# RX.net
KiCad netlist of a schematic drawn in Altium Designer
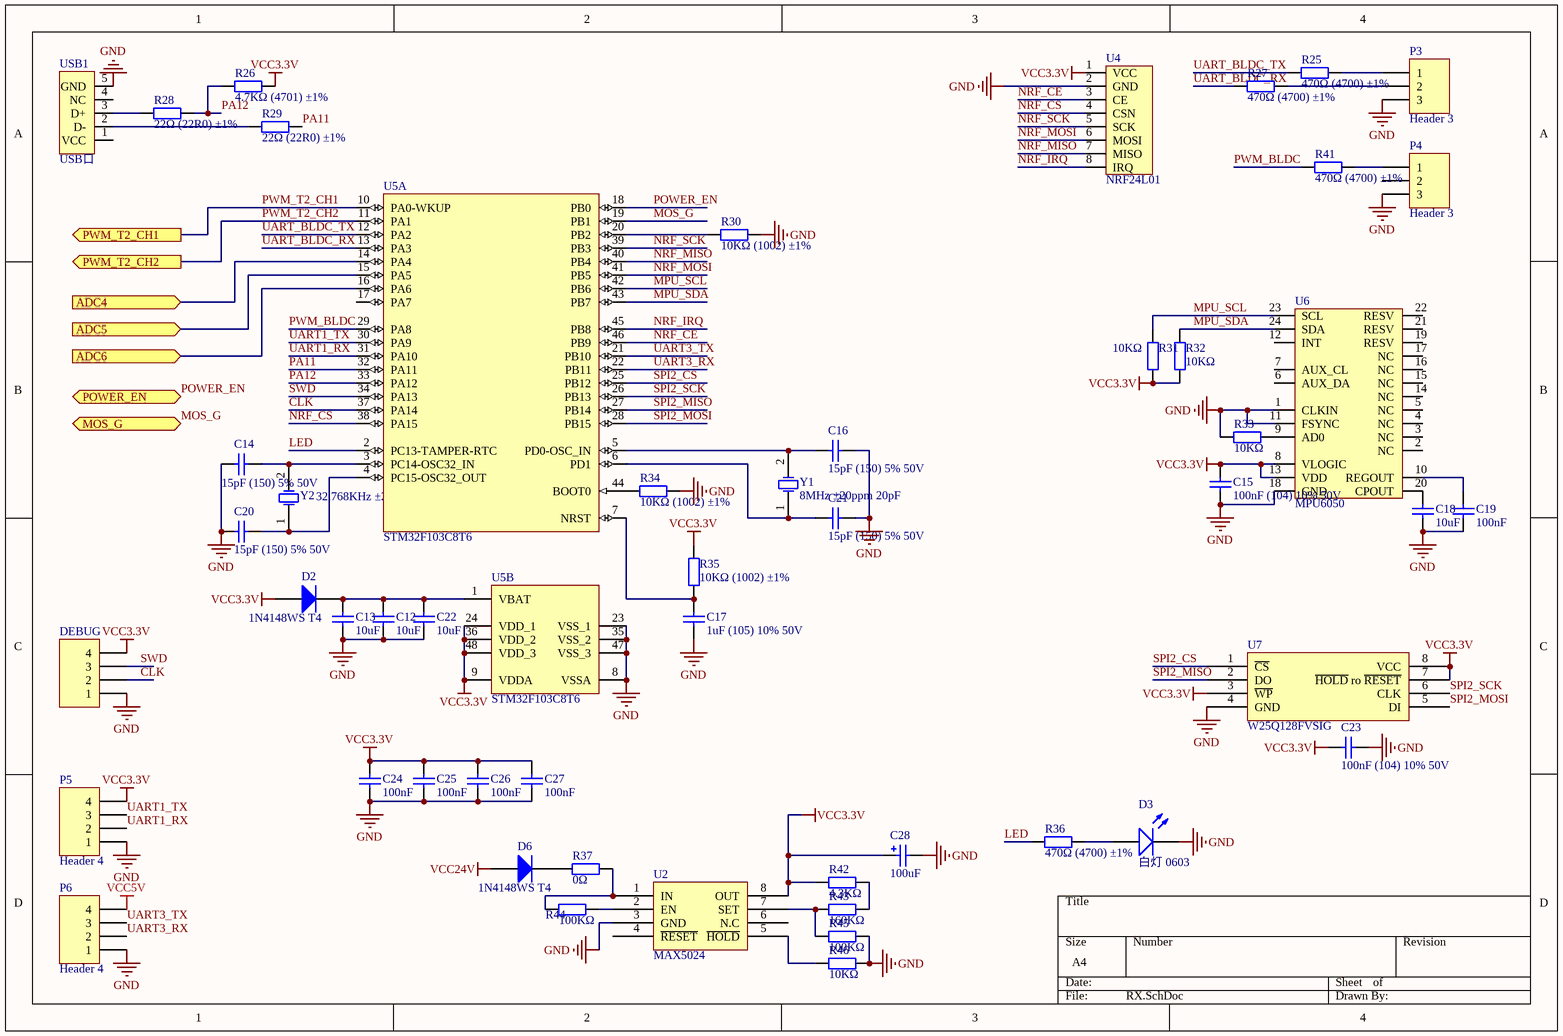
[diagram p0: RX.SchDoc]

(export (version "E")
  (design (tool "Eeschema 10.0.6"))
  (components
    (comp (ref "C12")
      (value "10uF")
      (footprint "0603_C")
      (description "贴片电容")
      (libsource (lib "Miscellaneous Devices LC") (part "0603 10uF (106) 10% 10V"))
    )
    (comp (ref "C13")
      (value "10uF")
      (footprint "0603_C")
      (description "贴片电容")
      (libsource (lib "Miscellaneous Devices LC") (part "0603 10uF (106) 10% 10V"))
    )
    (comp (ref "C14")
      (value "15pF (150) 5% 50V")
      (footprint "0603_C")
      (description "贴片电容")
      (libsource (lib "Miscellaneous Devices LC") (part "0603 15pF (150) 5% 50V"))
    )
    (comp (ref "C15")
      (value "100nF (104) 10% 50V")
      (footprint "0603_C")
      (description "贴片电容")
      (libsource (lib "Miscellaneous Devices LC") (part "0603 100nF (104) 10% 50V"))
    )
    (comp (ref "C16")
      (value "15pF (150) 5% 50V")
      (footprint "0603_C")
      (description "贴片电容")
      (libsource (lib "Miscellaneous Devices LC") (part "0603 15pF (150) 5% 50V"))
    )
    (comp (ref "C17")
      (value "1uF (105) 10% 50V")
      (footprint "0603_C")
      (description "贴片电容")
      (libsource (lib "Miscellaneous Devices LC") (part "0603 1uF (105) 10% 50V"))
    )
    (comp (ref "C18")
      (value "10uF")
      (footprint "0603_C")
      (description "贴片电容")
      (libsource (lib "Miscellaneous Devices LC") (part "0603 10uF (106) 10% 10V"))
    )
    (comp (ref "C19")
      (value "100nF")
      (footprint "0603_C")
      (description "贴片电容")
      (libsource (lib "Miscellaneous Devices LC") (part "0603 100nF (104) 10% 50V"))
    )
    (comp (ref "C20")
      (value "15pF (150) 5% 50V")
      (footprint "0603_C")
      (description "贴片电容")
      (libsource (lib "Miscellaneous Devices LC") (part "0603 15pF (150) 5% 50V"))
    )
    (comp (ref "C21")
      (value "15pF (150) 5% 50V")
      (footprint "0603_C")
      (description "贴片电容")
      (libsource (lib "Miscellaneous Devices LC") (part "0603 15pF (150) 5% 50V"))
    )
    (comp (ref "C22")
      (value "10uF")
      (footprint "0603_C")
      (description "贴片电容")
      (libsource (lib "Miscellaneous Devices LC") (part "0603 10uF (106) 10% 10V"))
    )
    (comp (ref "C23")
      (value "100nF (104) 10% 50V")
      (footprint "0603_C")
      (description "贴片电容")
      (libsource (lib "Miscellaneous Devices LC") (part "0603 100nF (104) 10% 50V"))
    )
    (comp (ref "C24")
      (value "100nF")
      (footprint "0603_C")
      (description "贴片电容")
      (libsource (lib "Miscellaneous Devices LC") (part "0603 100nF (104) 10% 50V"))
    )
    (comp (ref "C25")
      (value "100nF")
      (footprint "0603_C")
      (description "贴片电容")
      (libsource (lib "Miscellaneous Devices LC") (part "0603 100nF (104) 10% 50V"))
    )
    (comp (ref "C26")
      (value "100nF")
      (footprint "0603_C")
      (description "贴片电容")
      (libsource (lib "Miscellaneous Devices LC") (part "0603 100nF (104) 10% 50V"))
    )
    (comp (ref "C27")
      (value "100nF")
      (footprint "0603_C")
      (description "贴片电容")
      (libsource (lib "Miscellaneous Devices LC") (part "0603 100nF (104) 10% 50V"))
    )
    (comp (ref "C28")
      (value "100uF")
      (footprint "CASE-B_3528")
      (description "钽电容")
      (libsource (lib "Miscellaneous Devices LC") (part "3528 100uF (107) 10% 6.3V"))
    )
    (comp (ref "D2")
      (value "1N4148WS T4")
      (footprint "SOD-323")
      (description "二极管")
      (libsource (lib "Miscellaneous Devices LC") (part "SOD-323 1N4148WS T4"))
    )
    (comp (ref "D3")
      (value "白灯 0603")
      (footprint "0603_LED_S1")
      (description "发光二极管")
      (libsource (lib "Miscellaneous Devices LC") (part "0603 白灯"))
    )
    (comp (ref "D6")
      (value "1N4148WS T4")
      (footprint "SOD-323")
      (description "二极管")
      (libsource (lib "Miscellaneous Devices LC") (part "SOD-323 1N4148WS T4"))
    )
    (comp (ref "DEBUG")
      (value "Header 4")
      (footprint "HDR1X4")
      (description "Header, 4-Pin")
      (fields (field (name "PUBLISHER") "Altium Limited"))
      (libsource (lib "Miscellaneous Connectors") (part "Header 4"))
    )
    (comp (ref "P3")
      (value "Header 3")
      (footprint "HDR1X3")
      (description "Header, 3-Pin")
      (fields (field (name "PUBLISHER") "Altium Limited"))
      (libsource (lib "Miscellaneous Connectors") (part "Header 3"))
    )
    (comp (ref "P4")
      (value "Header 3")
      (footprint "HDR1X3")
      (description "Header, 3-Pin")
      (fields (field (name "PUBLISHER") "Altium Limited"))
      (libsource (lib "Miscellaneous Connectors") (part "Header 3"))
    )
    (comp (ref "P5")
      (value "Header 4")
      (footprint "HDR1X4")
      (description "Header, 4-Pin")
      (fields (field (name "PUBLISHER") "Altium Limited"))
      (libsource (lib "Miscellaneous Connectors") (part "Header 4"))
    )
    (comp (ref "P6")
      (value "Header 4")
      (footprint "HDR1X4")
      (description "Header, 4-Pin")
      (fields (field (name "PUBLISHER") "Altium Limited"))
      (libsource (lib "Miscellaneous Connectors") (part "Header 4"))
    )
    (comp (ref "R25")
      (value "470Ω (4700) ±1%")
      (footprint "0603_R")
      (description "贴片电阻")
      (libsource (lib "Miscellaneous Devices LC") (part "0603 470Ω (4700) 1%"))
    )
    (comp (ref "R26")
      (value "4.7KΩ (4701) ±1%")
      (footprint "0603_R")
      (description "贴片电阻")
      (libsource (lib "Miscellaneous Devices LC") (part "0603 4.7KΩ (4701) 1%"))
    )
    (comp (ref "R27")
      (value "470Ω (4700) ±1%")
      (footprint "0603_R")
      (description "贴片电阻")
      (libsource (lib "Miscellaneous Devices LC") (part "0603 470Ω (4700) 1%"))
    )
    (comp (ref "R28")
      (value "22Ω (22R0) ±1%")
      (footprint "0603_R")
      (description "贴片电阻")
      (libsource (lib "Miscellaneous Devices LC") (part "0603 22Ω (22R0) 1%"))
    )
    (comp (ref "R29")
      (value "22Ω (22R0) ±1%")
      (footprint "0603_R")
      (description "贴片电阻")
      (libsource (lib "Miscellaneous Devices LC") (part "0603 22Ω (22R0) 1%"))
    )
    (comp (ref "R30")
      (value "10KΩ (1002) ±1%")
      (footprint "0603_R")
      (description "贴片电阻")
      (libsource (lib "Miscellaneous Devices LC") (part "0603 10KΩ (1002) 1%"))
    )
    (comp (ref "R31")
      (value "10KΩ")
      (footprint "0603_R")
      (description "贴片电阻")
      (libsource (lib "") (part "0603 10KΩ (1002) 1%_1"))
    )
    (comp (ref "R32")
      (value "10KΩ")
      (footprint "0603_R")
      (description "贴片电阻")
      (libsource (lib "") (part "0603 10KΩ (1002) 1%_2"))
    )
    (comp (ref "R33")
      (value "10KΩ")
      (footprint "0603_R")
      (description "贴片电阻")
      (libsource (lib "Miscellaneous Devices LC") (part "0603 10KΩ (1002) 1%"))
    )
    (comp (ref "R34")
      (value "10KΩ (1002) ±1%")
      (footprint "0603_R")
      (description "贴片电阻")
      (libsource (lib "Miscellaneous Devices LC") (part "0603 10KΩ (1002) 1%"))
    )
    (comp (ref "R35")
      (value "10KΩ (1002) ±1%")
      (footprint "0603_R")
      (description "贴片电阻")
      (libsource (lib "") (part "0603 10KΩ (1002) 1%_1"))
    )
    (comp (ref "R36")
      (value "470Ω (4700) ±1%")
      (footprint "0603_R")
      (description "贴片电阻")
      (libsource (lib "Miscellaneous Devices LC") (part "0603 470Ω (4700) 1%"))
    )
    (comp (ref "R37")
      (value "0Ω")
      (footprint "0805_R")
      (description "贴片电阻")
      (libsource (lib "Miscellaneous Devices LC") (part "0805 0Ω (0R0) 1%"))
    )
    (comp (ref "R41")
      (value "470Ω (4700) ±1%")
      (footprint "0603_R")
      (description "贴片电阻")
      (libsource (lib "Miscellaneous Devices LC") (part "0603 470Ω (4700) 1%"))
    )
    (comp (ref "R42")
      (value "4.3KΩ")
      (footprint "0603_R")
      (description "贴片电阻")
      (libsource (lib "Miscellaneous Devices LC") (part "0603 4.3KΩ (4301) 1%"))
    )
    (comp (ref "R43")
      (value "160KΩ")
      (footprint "0603_R")
      (description "贴片电阻")
      (libsource (lib "Miscellaneous Devices LC") (part "0603 160KΩ (1603) 1%"))
    )
    (comp (ref "R44")
      (value "100KΩ")
      (footprint "0603_R")
      (description "贴片电阻")
      (libsource (lib "Miscellaneous Devices LC") (part "0603 100KΩ (1003) 1%"))
    )
    (comp (ref "R45")
      (value "100KΩ")
      (footprint "0603_R")
      (description "贴片电阻")
      (libsource (lib "Miscellaneous Devices LC") (part "0603 100KΩ (1003) 1%"))
    )
    (comp (ref "R46")
      (value "10KΩ")
      (footprint "0603_R")
      (description "贴片电阻")
      (libsource (lib "Miscellaneous Devices LC") (part "0603 10KΩ (1002) 1%"))
    )
    (comp (ref "U2")
      (value "MAX5024")
      (footprint "SOIC-8_EP_150mil")
      (description "LDO 65Vmax")
      (libsource (lib "MySchlib") (part "MAX5024"))
    )
    (comp (ref "U4")
      (value "NRF24L01")
      (footprint "miniNRF24L01")
      (libsource (lib "MySchlib") (part "NRF24L01"))
    )
    (comp (ref "U5")
      (value "STM32F103C8T6")
      (footprint "LQFP-48_7x7x05P")
      (description "ARM")
      (libsource (lib "Miscellaneous Devices LC") (part "STM32F103C8T6"))
    )
    (comp (ref "U6")
      (value "MPU6050")
      (footprint "QFN24")
      (description "9轴运动处理传感器")
      (libsource (lib "MySchlib") (part "MPU6050"))
    )
    (comp (ref "U7")
      (value "W25Q128FVSIG")
      (footprint "SOIC-8_208mil")
      (description "Flash ROM")
      (libsource (lib "Miscellaneous Devices LC") (part "W25Q128FVSIG"))
    )
    (comp (ref "USB1") (value "USB口") (footprint "MICRO USB") (libsource (lib "MySchlib") (part "USB口")))
    (comp (ref "Y1")
      (value "8MHz ±20ppm 20pF")
      (footprint "SMD-3215_2P FC - 135")
      (description "贴片晶振")
      (libsource (lib "Miscellaneous Devices LC") (part "SMD-5032_2P 8MHz 20ppm 20pF"))
    )
    (comp (ref "Y2")
      (value "32.768KHz ±20ppm 12.5pF")
      (footprint "SMD-3215_2P FC - 135")
      (description "贴片晶振")
      (libsource (lib "Miscellaneous Devices LC") (part "SMD-3215_2P 32.768KHz 20ppm 12.5pF"))
    )
  )
  (nets
    (net (code "1") (name "/ADC4") (class "Default")
      (node (ref "U5") (pin "14") (pinfunction "PA4_14") (pintype "bidirectional"))
    )
    (net (code "2") (name "/ADC5") (class "Default")
      (node (ref "U5") (pin "15") (pinfunction "PA5_15") (pintype "bidirectional"))
    )
    (net (code "3") (name "/ADC6") (class "Default")
      (node (ref "U5") (pin "16") (pinfunction "PA6_16") (pintype "bidirectional"))
    )
    (net (code "4") (name "/CLK") (class "Default")
      (node (ref "DEBUG") (pin "2") (pinfunction "2_2") (pintype "passive"))
      (node (ref "U5") (pin "37") (pinfunction "PA14_37") (pintype "bidirectional"))
    )
    (net (code "5") (name "/LED") (class "Default")
      (node (ref "R36") (pin "1") (pinfunction "1_1") (pintype "passive"))
      (node (ref "U5") (pin "2") (pinfunction "PC13-TAMPER-RTC_2") (pintype "bidirectional"))
    )
    (net (code "6") (name "/MOS_G") (class "Default")
      (node (ref "U5") (pin "19") (pinfunction "PB1_19") (pintype "bidirectional"))
    )
    (net (code "7") (name "/MPU_SCL") (class "Default")
      (node (ref "R31") (pin "2") (pinfunction "2_2") (pintype "passive"))
      (node (ref "U5") (pin "42") (pinfunction "PB6_42") (pintype "bidirectional"))
      (node (ref "U6") (pin "23") (pinfunction "SCL_23") (pintype "passive"))
    )
    (net (code "8") (name "/MPU_SDA") (class "Default")
      (node (ref "R32") (pin "1") (pinfunction "1_1") (pintype "passive"))
      (node (ref "U5") (pin "43") (pinfunction "PB7_43") (pintype "bidirectional"))
      (node (ref "U6") (pin "24") (pinfunction "SDA_24") (pintype "passive"))
    )
    (net (code "9") (name "/NRF_CE") (class "Default")
      (node (ref "U4") (pin "3") (pinfunction "CE_3") (pintype "passive"))
      (node (ref "U5") (pin "46") (pinfunction "PB9_46") (pintype "bidirectional"))
    )
    (net (code "10") (name "/NRF_CS") (class "Default")
      (node (ref "U4") (pin "4") (pinfunction "CSN_4") (pintype "passive"))
      (node (ref "U5") (pin "38") (pinfunction "PA15_38") (pintype "bidirectional"))
    )
    (net (code "11") (name "/NRF_IRQ") (class "Default")
      (node (ref "U4") (pin "8") (pinfunction "IRQ_8") (pintype "passive"))
      (node (ref "U5") (pin "45") (pinfunction "PB8_45") (pintype "bidirectional"))
    )
    (net (code "12") (name "/NRF_MISO") (class "Default")
      (node (ref "U4") (pin "7") (pinfunction "MISO_7") (pintype "passive"))
      (node (ref "U5") (pin "40") (pinfunction "PB4_40") (pintype "bidirectional"))
    )
    (net (code "13") (name "/NRF_MOSI") (class "Default")
      (node (ref "U4") (pin "6") (pinfunction "MOSI_6") (pintype "passive"))
      (node (ref "U5") (pin "41") (pinfunction "PB5_41") (pintype "bidirectional"))
    )
    (net (code "14") (name "/NRF_SCK") (class "Default")
      (node (ref "U4") (pin "5") (pinfunction "SCK_5") (pintype "passive"))
      (node (ref "U5") (pin "39") (pinfunction "PB3_39") (pintype "bidirectional"))
    )
    (net (code "15") (name "/PA11") (class "Default")
      (node (ref "R29") (pin "2") (pinfunction "2_2") (pintype "passive"))
      (node (ref "U5") (pin "32") (pinfunction "PA11_32") (pintype "bidirectional"))
    )
    (net (code "16") (name "/PA12") (class "Default")
      (node (ref "R26") (pin "1") (pinfunction "1_1") (pintype "passive"))
      (node (ref "R28") (pin "2") (pinfunction "2_2") (pintype "passive"))
      (node (ref "U5") (pin "33") (pinfunction "PA12_33") (pintype "bidirectional"))
    )
    (net (code "17") (name "/POWER_EN") (class "Default")
      (node (ref "U5") (pin "18") (pinfunction "PB0_18") (pintype "bidirectional"))
    )
    (net (code "18") (name "/PWM_BLDC") (class "Default")
      (node (ref "R41") (pin "1") (pinfunction "1_1") (pintype "passive"))
      (node (ref "U5") (pin "29") (pinfunction "PA8_29") (pintype "bidirectional"))
    )
    (net (code "19") (name "/PWM_T2_CH1") (class "Default")
      (node (ref "U5") (pin "10") (pinfunction "PA0-WKUP_10") (pintype "bidirectional"))
    )
    (net (code "20") (name "/PWM_T2_CH2") (class "Default")
      (node (ref "U5") (pin "11") (pinfunction "PA1_11") (pintype "bidirectional"))
    )
    (net (code "21") (name "/SPI2_CS") (class "Default")
      (node (ref "U5") (pin "25") (pinfunction "PB12_25") (pintype "bidirectional"))
      (node (ref "U7") (pin "1") (pinfunction "~{CS}_1") (pintype "passive"))
    )
    (net (code "22") (name "/SPI2_MISO") (class "Default")
      (node (ref "U5") (pin "27") (pinfunction "PB14_27") (pintype "bidirectional"))
      (node (ref "U7") (pin "2") (pinfunction "DO_2") (pintype "passive"))
    )
    (net (code "23") (name "/SPI2_MOSI") (class "Default")
      (node (ref "U5") (pin "28") (pinfunction "PB15_28") (pintype "bidirectional"))
      (node (ref "U7") (pin "5") (pinfunction "DI_5") (pintype "passive"))
    )
    (net (code "24") (name "/SPI2_SCK") (class "Default")
      (node (ref "U5") (pin "26") (pinfunction "PB13_26") (pintype "bidirectional"))
      (node (ref "U7") (pin "6") (pinfunction "CLK_6") (pintype "passive"))
    )
    (net (code "25") (name "/SWD") (class "Default")
      (node (ref "DEBUG") (pin "3") (pinfunction "3_3") (pintype "passive"))
      (node (ref "U5") (pin "34") (pinfunction "PA13_34") (pintype "bidirectional"))
    )
    (net (code "26") (name "/UART1_RX") (class "Default")
      (node (ref "P5") (pin "2") (pinfunction "2_2") (pintype "passive"))
      (node (ref "U5") (pin "31") (pinfunction "PA10_31") (pintype "bidirectional"))
    )
    (net (code "27") (name "/UART1_TX") (class "Default")
      (node (ref "P5") (pin "3") (pinfunction "3_3") (pintype "passive"))
      (node (ref "U5") (pin "30") (pinfunction "PA9_30") (pintype "bidirectional"))
    )
    (net (code "28") (name "/UART3_RX") (class "Default")
      (node (ref "P6") (pin "2") (pinfunction "2_2") (pintype "passive"))
      (node (ref "U5") (pin "22") (pinfunction "PB11_22") (pintype "bidirectional"))
    )
    (net (code "29") (name "/UART3_TX") (class "Default")
      (node (ref "P6") (pin "3") (pinfunction "3_3") (pintype "passive"))
      (node (ref "U5") (pin "21") (pinfunction "PB10_21") (pintype "bidirectional"))
    )
    (net (code "30") (name "/UART_BLDC_RX") (class "Default")
      (node (ref "R27") (pin "1") (pinfunction "1_1") (pintype "passive"))
      (node (ref "U5") (pin "13") (pinfunction "PA3_13") (pintype "bidirectional"))
    )
    (net (code "31") (name "/UART_BLDC_TX") (class "Default")
      (node (ref "R25") (pin "1") (pinfunction "1_1") (pintype "passive"))
      (node (ref "U5") (pin "12") (pinfunction "PA2_12") (pintype "bidirectional"))
    )
    (net (code "32") (name "GND") (class "Default")
      (node (ref "C12") (pin "1") (pinfunction "1_1") (pintype "passive"))
      (node (ref "C13") (pin "1") (pinfunction "1_1") (pintype "passive"))
      (node (ref "C14") (pin "1") (pinfunction "1_1") (pintype "passive"))
      (node (ref "C15") (pin "2") (pinfunction "2_2") (pintype "passive"))
      (node (ref "C16") (pin "2") (pinfunction "2_2") (pintype "passive"))
      (node (ref "C17") (pin "1") (pinfunction "1_1") (pintype "passive"))
      (node (ref "C18") (pin "1") (pinfunction "1_1") (pintype "passive"))
      (node (ref "C19") (pin "2") (pinfunction "2_2") (pintype "passive"))
      (node (ref "C20") (pin "1") (pinfunction "1_1") (pintype "passive"))
      (node (ref "C21") (pin "2") (pinfunction "2_2") (pintype "passive"))
      (node (ref "C22") (pin "1") (pinfunction "1_1") (pintype "passive"))
      (node (ref "C23") (pin "1") (pinfunction "1_1") (pintype "passive"))
      (node (ref "C24") (pin "2") (pinfunction "2_2") (pintype "passive"))
      (node (ref "C25") (pin "2") (pinfunction "2_2") (pintype "passive"))
      (node (ref "C26") (pin "2") (pinfunction "2_2") (pintype "passive"))
      (node (ref "C27") (pin "2") (pinfunction "2_2") (pintype "passive"))
      (node (ref "C28") (pin "2") (pinfunction "2_2") (pintype "passive"))
      (node (ref "D3") (pin "K") (pinfunction "K_K") (pintype "passive"))
      (node (ref "DEBUG") (pin "1") (pinfunction "1_1") (pintype "passive"))
      (node (ref "P3") (pin "3") (pinfunction "3_3") (pintype "passive"))
      (node (ref "P4") (pin "3") (pinfunction "3_3") (pintype "passive"))
      (node (ref "P5") (pin "1") (pinfunction "1_1") (pintype "passive"))
      (node (ref "P6") (pin "1") (pinfunction "1_1") (pintype "passive"))
      (node (ref "R30") (pin "2") (pinfunction "2_2") (pintype "passive"))
      (node (ref "R33") (pin "1") (pinfunction "1_1") (pintype "passive"))
      (node (ref "R34") (pin "2") (pinfunction "2_2") (pintype "passive"))
      (node (ref "R45") (pin "2") (pinfunction "2_2") (pintype "passive"))
      (node (ref "R46") (pin "2") (pinfunction "2_2") (pintype "passive"))
      (node (ref "U2") (pin "3") (pinfunction "GND_3") (pintype "passive"))
      (node (ref "U4") (pin "2") (pinfunction "GND_2") (pintype "passive"))
      (node (ref "U5") (pin "23") (pinfunction "VSS_1_23") (pintype "power_in"))
      (node (ref "U5") (pin "35") (pinfunction "VSS_2_35") (pintype "power_in"))
      (node (ref "U5") (pin "47") (pinfunction "VSS_3_47") (pintype "power_in"))
      (node (ref "U5") (pin "8") (pinfunction "VSSA_8") (pintype "power_in"))
      (node (ref "U6") (pin "1") (pinfunction "CLKIN_1") (pintype "passive"))
      (node (ref "U6") (pin "11") (pinfunction "FSYNC_11") (pintype "passive"))
      (node (ref "U6") (pin "18") (pinfunction "GND_18") (pintype "passive"))
      (node (ref "U7") (pin "4") (pinfunction "GND_4") (pintype "passive"))
      (node (ref "USB1") (pin "5") (pinfunction "GND_5") (pintype "passive"))
    )
    (net (code "33") (name "Net-(D2-K)") (class "Default")
      (node (ref "C12") (pin "2") (pinfunction "2_2") (pintype "passive"))
      (node (ref "C13") (pin "2") (pinfunction "2_2") (pintype "passive"))
      (node (ref "C22") (pin "2") (pinfunction "2_2") (pintype "passive"))
      (node (ref "D2") (pin "2") (pinfunction "K_2") (pintype "passive"))
      (node (ref "U5") (pin "1") (pinfunction "VBAT_1") (pintype "power_in"))
    )
    (net (code "34") (name "Net-(D3-PadA)") (class "Default")
      (node (ref "D3") (pin "A") (pinfunction "A_A") (pintype "passive"))
      (node (ref "R36") (pin "2") (pinfunction "2_2") (pintype "passive"))
    )
    (net (code "35") (name "Net-(D6-K)") (class "Default")
      (node (ref "D6") (pin "2") (pinfunction "K_2") (pintype "passive"))
      (node (ref "R37") (pin "1") (pinfunction "1_1") (pintype "passive"))
    )
    (net (code "36") (name "Net-(P3-Pad1)") (class "Default")
      (node (ref "P3") (pin "1") (pinfunction "1_1") (pintype "passive"))
      (node (ref "R25") (pin "2") (pinfunction "2_2") (pintype "passive"))
    )
    (net (code "37") (name "Net-(P3-Pad2)") (class "Default")
      (node (ref "P3") (pin "2") (pinfunction "2_2") (pintype "passive"))
      (node (ref "R27") (pin "2") (pinfunction "2_2") (pintype "passive"))
    )
    (net (code "38") (name "Net-(P4-Pad1)") (class "Default")
      (node (ref "P4") (pin "1") (pinfunction "1_1") (pintype "passive"))
      (node (ref "R41") (pin "2") (pinfunction "2_2") (pintype "passive"))
    )
    (net (code "39") (name "Net-(R42-Pad2)") (class "Default")
      (node (ref "R42") (pin "2") (pinfunction "2_2") (pintype "passive"))
      (node (ref "R43") (pin "2") (pinfunction "2_2") (pintype "passive"))
    )
    (net (code "40") (name "Net-(U2-EN)") (class "Default")
      (node (ref "R44") (pin "2") (pinfunction "2_2") (pintype "passive"))
      (node (ref "U2") (pin "2") (pinfunction "EN_2") (pintype "passive"))
    )
    (net (code "41") (name "Net-(U2-IN)") (class "Default")
      (node (ref "R37") (pin "2") (pinfunction "2_2") (pintype "passive"))
      (node (ref "R44") (pin "1") (pinfunction "1_1") (pintype "passive"))
      (node (ref "U2") (pin "1") (pinfunction "IN_1") (pintype "passive"))
    )
    (net (code "42") (name "Net-(U2-SET)") (class "Default")
      (node (ref "R43") (pin "1") (pinfunction "1_1") (pintype "passive"))
      (node (ref "R45") (pin "1") (pinfunction "1_1") (pintype "passive"))
      (node (ref "U2") (pin "7") (pinfunction "SET_7") (pintype "passive"))
    )
    (net (code "43") (name "Net-(U2-~{HOLD})") (class "Default")
      (node (ref "R46") (pin "1") (pinfunction "1_1") (pintype "passive"))
      (node (ref "U2") (pin "5") (pinfunction "~{HOLD}_5") (pintype "passive"))
    )
    (net (code "44") (name "Net-(U5A-BOOT0)") (class "Default")
      (node (ref "R34") (pin "1") (pinfunction "1_1") (pintype "passive"))
      (node (ref "U5") (pin "44") (pinfunction "BOOT0_44") (pintype "input"))
    )
    (net (code "45") (name "Net-(U5A-NRST)") (class "Default")
      (node (ref "C17") (pin "2") (pinfunction "2_2") (pintype "passive"))
      (node (ref "R35") (pin "1") (pinfunction "1_1") (pintype "passive"))
      (node (ref "U5") (pin "7") (pinfunction "NRST_7") (pintype "bidirectional"))
    )
    (net (code "46") (name "Net-(U5A-PB2)") (class "Default")
      (node (ref "R30") (pin "1") (pinfunction "1_1") (pintype "passive"))
      (node (ref "U5") (pin "20") (pinfunction "PB2_20") (pintype "bidirectional"))
    )
    (net (code "47") (name "Net-(U5A-PC14-OSC32_IN)") (class "Default")
      (node (ref "C14") (pin "2") (pinfunction "2_2") (pintype "passive"))
      (node (ref "U5") (pin "3") (pinfunction "PC14-OSC32_IN_3") (pintype "bidirectional"))
      (node (ref "Y2") (pin "2") (pinfunction "OSC2_2") (pintype "passive"))
    )
    (net (code "48") (name "Net-(U5A-PC15-OSC32_OUT)") (class "Default")
      (node (ref "C20") (pin "2") (pinfunction "2_2") (pintype "passive"))
      (node (ref "U5") (pin "4") (pinfunction "PC15-OSC32_OUT_4") (pintype "bidirectional"))
      (node (ref "Y2") (pin "1") (pinfunction "OSC1_1") (pintype "passive"))
    )
    (net (code "49") (name "Net-(U5A-PD0-OSC_IN)") (class "Default")
      (node (ref "C16") (pin "1") (pinfunction "1_1") (pintype "passive"))
      (node (ref "U5") (pin "5") (pinfunction "PD0-OSC_IN_5") (pintype "bidirectional"))
      (node (ref "Y1") (pin "2") (pinfunction "OSC2_2") (pintype "passive"))
    )
    (net (code "50") (name "Net-(U5A-PD1)") (class "Default")
      (node (ref "C21") (pin "1") (pinfunction "1_1") (pintype "passive"))
      (node (ref "U5") (pin "6") (pinfunction "PD1_6") (pintype "bidirectional"))
      (node (ref "Y1") (pin "1") (pinfunction "OSC1_1") (pintype "passive"))
    )
    (net (code "51") (name "Net-(U6-AD0)") (class "Default")
      (node (ref "R33") (pin "2") (pinfunction "2_2") (pintype "passive"))
      (node (ref "U6") (pin "9") (pinfunction "AD0_9") (pintype "passive"))
    )
    (net (code "52") (name "Net-(U6-CPOUT)") (class "Default")
      (node (ref "C18") (pin "2") (pinfunction "2_2") (pintype "passive"))
      (node (ref "U6") (pin "20") (pinfunction "CPOUT_20") (pintype "passive"))
    )
    (net (code "53") (name "Net-(U6-REGOUT)") (class "Default")
      (node (ref "C19") (pin "1") (pinfunction "1_1") (pintype "passive"))
      (node (ref "U6") (pin "10") (pinfunction "REGOUT_10") (pintype "passive"))
    )
    (net (code "54") (name "Net-(USB1-D+)") (class "Default")
      (node (ref "R28") (pin "1") (pinfunction "1_1") (pintype "passive"))
      (node (ref "USB1") (pin "3") (pinfunction "D+_3") (pintype "passive"))
    )
    (net (code "55") (name "Net-(USB1-D-)") (class "Default")
      (node (ref "R29") (pin "1") (pinfunction "1_1") (pintype "passive"))
      (node (ref "USB1") (pin "2") (pinfunction "D-_2") (pintype "passive"))
    )
    (net (code "56") (name "VCC3.3V") (class "Default")
      (node (ref "C15") (pin "1") (pinfunction "1_1") (pintype "passive"))
      (node (ref "C23") (pin "2") (pinfunction "2_2") (pintype "passive"))
      (node (ref "C24") (pin "1") (pinfunction "1_1") (pintype "passive"))
      (node (ref "C25") (pin "1") (pinfunction "1_1") (pintype "passive"))
      (node (ref "C26") (pin "1") (pinfunction "1_1") (pintype "passive"))
      (node (ref "C27") (pin "1") (pinfunction "1_1") (pintype "passive"))
      (node (ref "C28") (pin "1") (pinfunction "1_1") (pintype "passive"))
      (node (ref "D2") (pin "1") (pinfunction "A_1") (pintype "passive"))
      (node (ref "DEBUG") (pin "4") (pinfunction "4_4") (pintype "passive"))
      (node (ref "P5") (pin "4") (pinfunction "4_4") (pintype "passive"))
      (node (ref "R26") (pin "2") (pinfunction "2_2") (pintype "passive"))
      (node (ref "R31") (pin "1") (pinfunction "1_1") (pintype "passive"))
      (node (ref "R32") (pin "2") (pinfunction "2_2") (pintype "passive"))
      (node (ref "R35") (pin "2") (pinfunction "2_2") (pintype "passive"))
      (node (ref "R42") (pin "1") (pinfunction "1_1") (pintype "passive"))
      (node (ref "U2") (pin "8") (pinfunction "OUT_8") (pintype "passive"))
      (node (ref "U4") (pin "1") (pinfunction "VCC_1") (pintype "passive"))
      (node (ref "U5") (pin "24") (pinfunction "VDD_1_24") (pintype "power_in"))
      (node (ref "U5") (pin "36") (pinfunction "VDD_2_36") (pintype "power_in"))
      (node (ref "U5") (pin "48") (pinfunction "VDD_3_48") (pintype "power_in"))
      (node (ref "U5") (pin "9") (pinfunction "VDDA_9") (pintype "power_in"))
      (node (ref "U6") (pin "13") (pinfunction "VDD_13") (pintype "passive"))
      (node (ref "U6") (pin "8") (pinfunction "VLOGIC_8") (pintype "passive"))
      (node (ref "U7") (pin "3") (pinfunction "~{WP}_3") (pintype "passive"))
      (node (ref "U7") (pin "7") (pinfunction "~{HOLD}_ro_~{RESET}_7") (pintype "passive"))
      (node (ref "U7") (pin "8") (pinfunction "VCC_8") (pintype "passive"))
    )
    (net (code "57") (name "VCC5V") (class "Default")
      (node (ref "P6") (pin "4") (pinfunction "4_4") (pintype "passive"))
    )
    (net (code "58") (name "VCC24V") (class "Default")
      (node (ref "D6") (pin "1") (pinfunction "A_1") (pintype "passive"))
    )
    (net (code "59") (name "unconnected-(P4-Pad2)") (class "Default")
      (node (ref "P4") (pin "2") (pinfunction "2_2") (pintype "passive"))
    )
    (net (code "60") (name "unconnected-(U2-N.C-Pad6)") (class "Default")
      (node (ref "U2") (pin "6") (pinfunction "N.C_6") (pintype "passive"))
    )
    (net (code "61") (name "unconnected-(U2-~{RESET}-Pad4)") (class "Default")
      (node (ref "U2") (pin "4") (pinfunction "~{RESET}_4") (pintype "passive"))
    )
    (net (code "62") (name "unconnected-(U5A-PA7-Pad17)") (class "Default")
      (node (ref "U5") (pin "17") (pinfunction "PA7_17") (pintype "bidirectional"))
    )
    (net (code "63") (name "unconnected-(U6-AUX_CL-Pad7)") (class "Default")
      (node (ref "U6") (pin "7") (pinfunction "AUX_CL_7") (pintype "passive"))
    )
    (net (code "64") (name "unconnected-(U6-AUX_DA-Pad6)") (class "Default")
      (node (ref "U6") (pin "6") (pinfunction "AUX_DA_6") (pintype "passive"))
    )
    (net (code "65") (name "unconnected-(U6-INT-Pad12)") (class "Default")
      (node (ref "U6") (pin "12") (pinfunction "INT_12") (pintype "passive"))
    )
    (net (code "66") (name "unconnected-(U6-NC-Pad2)") (class "Default")
      (node (ref "U6") (pin "2") (pinfunction "NC_2") (pintype "passive"))
    )
    (net (code "67") (name "unconnected-(U6-NC-Pad3)") (class "Default")
      (node (ref "U6") (pin "3") (pinfunction "NC_3") (pintype "passive"))
    )
    (net (code "68") (name "unconnected-(U6-NC-Pad4)") (class "Default")
      (node (ref "U6") (pin "4") (pinfunction "NC_4") (pintype "passive"))
    )
    (net (code "69") (name "unconnected-(U6-NC-Pad5)") (class "Default")
      (node (ref "U6") (pin "5") (pinfunction "NC_5") (pintype "passive"))
    )
    (net (code "70") (name "unconnected-(U6-NC-Pad14)") (class "Default")
      (node (ref "U6") (pin "14") (pinfunction "NC_14") (pintype "passive"))
    )
    (net (code "71") (name "unconnected-(U6-NC-Pad15)") (class "Default")
      (node (ref "U6") (pin "15") (pinfunction "NC_15") (pintype "passive"))
    )
    (net (code "72") (name "unconnected-(U6-NC-Pad16)") (class "Default")
      (node (ref "U6") (pin "16") (pinfunction "NC_16") (pintype "passive"))
    )
    (net (code "73") (name "unconnected-(U6-NC-Pad17)") (class "Default")
      (node (ref "U6") (pin "17") (pinfunction "NC_17") (pintype "passive"))
    )
    (net (code "74") (name "unconnected-(U6-RESV-Pad19)") (class "Default")
      (node (ref "U6") (pin "19") (pinfunction "RESV_19") (pintype "passive"))
    )
    (net (code "75") (name "unconnected-(U6-RESV-Pad21)") (class "Default")
      (node (ref "U6") (pin "21") (pinfunction "RESV_21") (pintype "passive"))
    )
    (net (code "76") (name "unconnected-(U6-RESV-Pad22)") (class "Default")
      (node (ref "U6") (pin "22") (pinfunction "RESV_22") (pintype "passive"))
    )
    (net (code "77") (name "unconnected-(USB1-NC-Pad4)") (class "Default")
      (node (ref "USB1") (pin "4") (pinfunction "NC_4") (pintype "passive"))
    )
    (net (code "78") (name "unconnected-(USB1-VCC-Pad1)") (class "Default")
      (node (ref "USB1") (pin "1") (pinfunction "VCC_1") (pintype "passive"))
    )
  )
)
